# C64_PSU.net
KiCad netlist of a schematic drawn in EAGLE
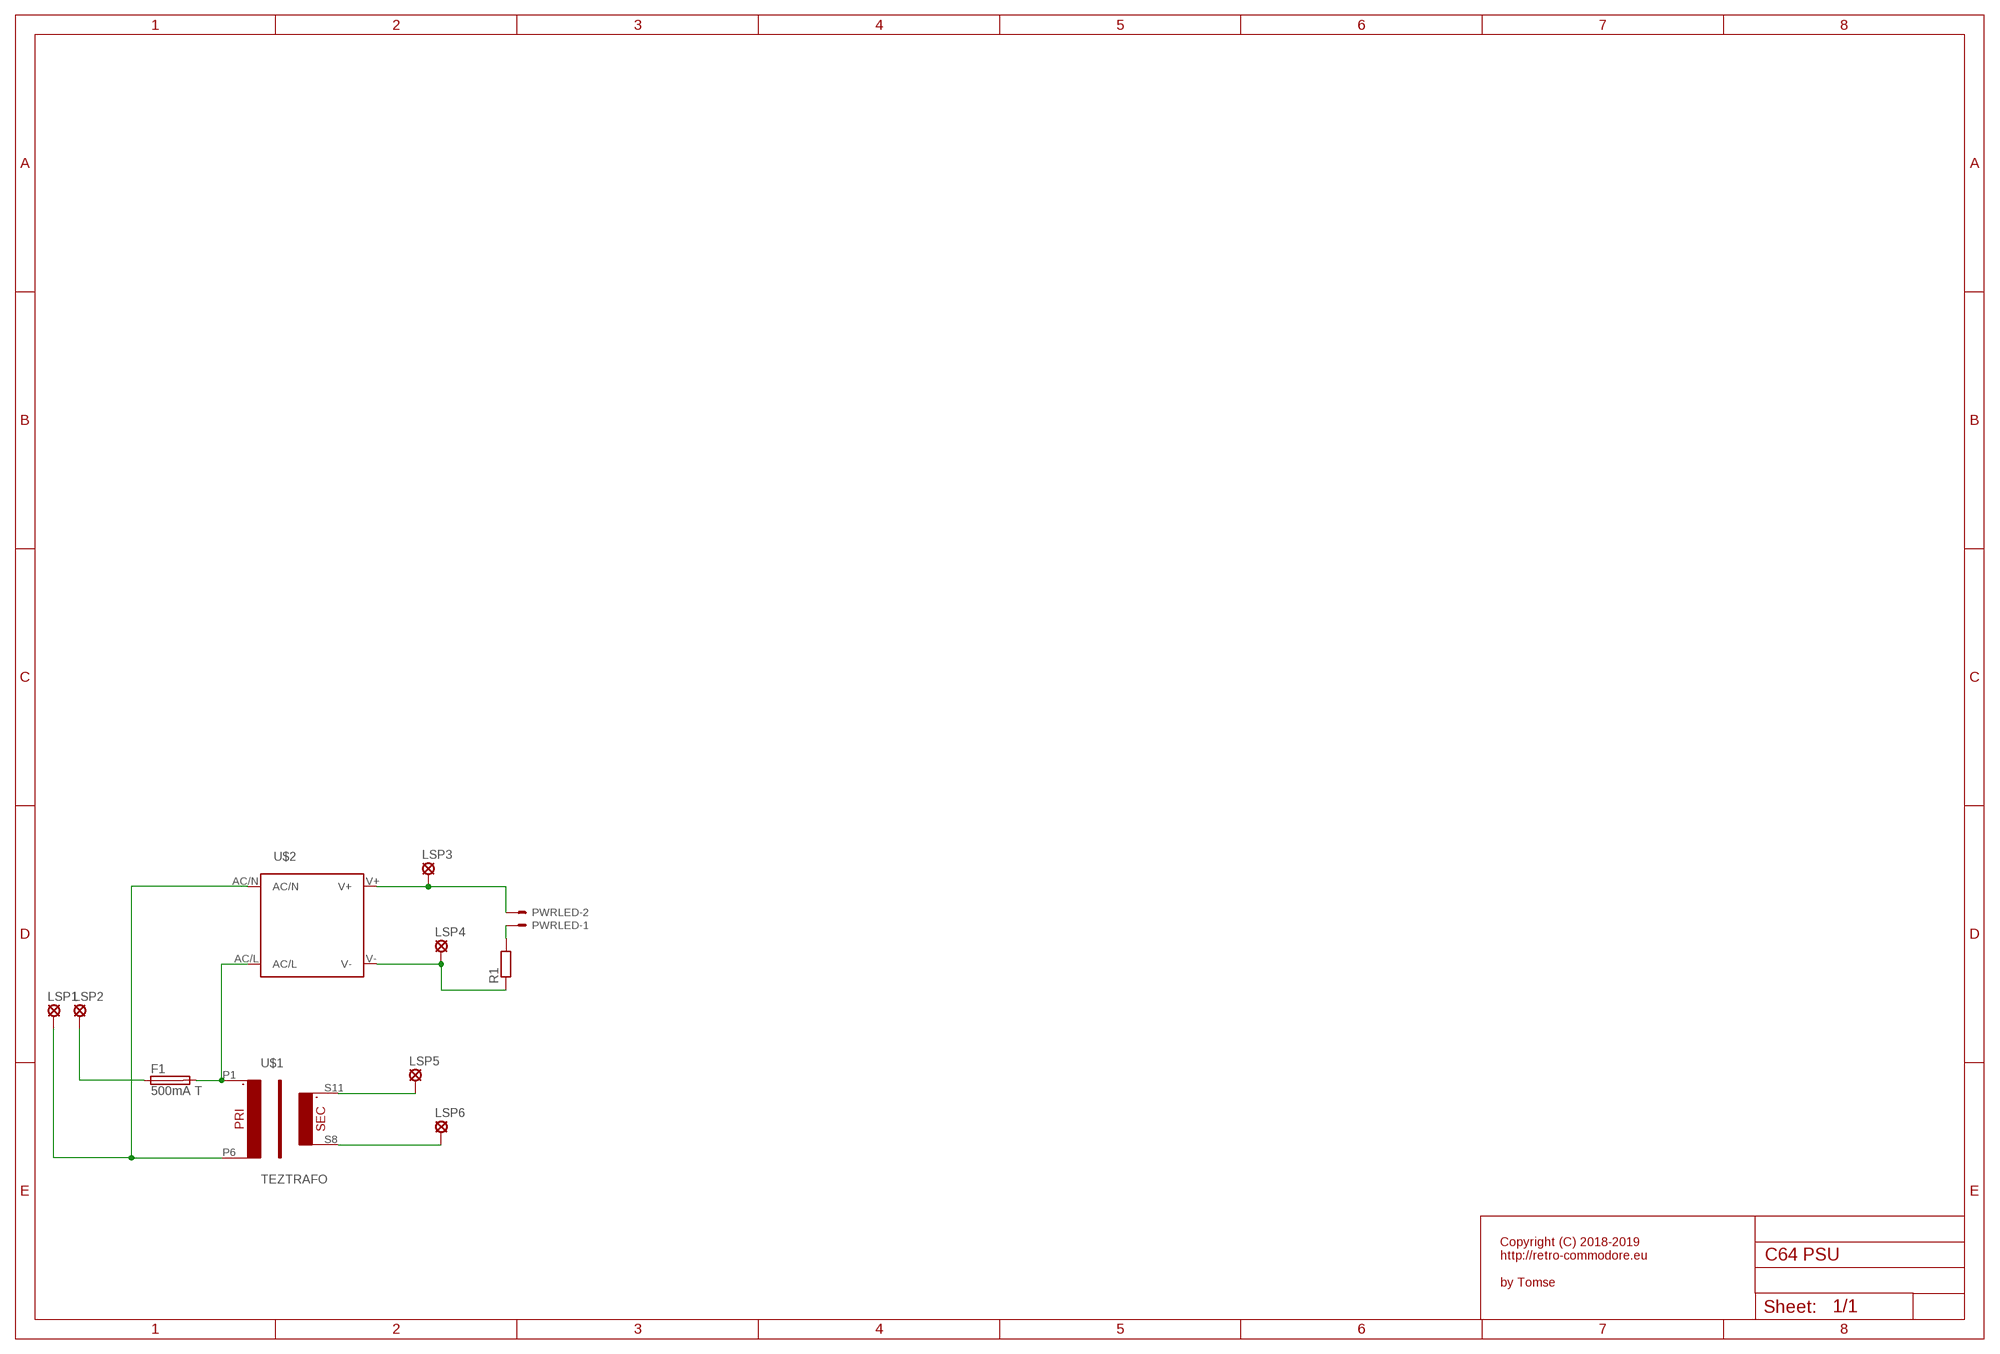
[diagram p0: schematic, sheet 1]

(export (version "E")
  (design (tool "Eeschema 10.0.6"))
  (components
    (comp (ref "F1")
      (value "500mA T")
      (footprint "eagle-import:SH22,5")
      (libsource (lib "eagle-import") (part "FUSESH22,5"))
    )
    (comp (ref "LSP1")
      (value "SE14")
      (footprint "eagle-import:SE14")
      (libsource (lib "eagle-import") (part "SE14"))
    )
    (comp (ref "LSP2")
      (value "SE14")
      (footprint "eagle-import:SE14")
      (libsource (lib "eagle-import") (part "SE14"))
    )
    (comp (ref "LSP3")
      (value "SE14")
      (footprint "eagle-import:SE14")
      (libsource (lib "eagle-import") (part "SE14"))
    )
    (comp (ref "LSP4")
      (value "SE14")
      (footprint "eagle-import:SE14")
      (libsource (lib "eagle-import") (part "SE14"))
    )
    (comp (ref "LSP5")
      (value "SE14")
      (footprint "eagle-import:SE14")
      (libsource (lib "eagle-import") (part "SE14"))
    )
    (comp (ref "LSP6")
      (value "SE14")
      (footprint "eagle-import:SE14")
      (libsource (lib "eagle-import") (part "SE14"))
    )
    (comp (ref "PWRLED")
      (value "22-23-2021")
      (footprint "eagle-import:22-23-2021")
      (fields (field (name "MF") "MOLEX"))
      (libsource (lib "eagle-import") (part "22-23-2021"))
    )
    (comp (ref "R1")
      (value "R-EU_0207/10")
      (footprint "eagle-import:0207_10")
      (libsource (lib "eagle-import") (part "R-EU_0207/10"))
    )
    (comp (ref "U$1")
      (value "TEZTRAFO")
      (footprint "eagle-import:TEZ10_D230_9V")
      (libsource (lib "eagle-import") (part "TEZTRAFO"))
    )
    (comp (ref "U$2")
      (value "IRM_15/20IRM_15/20")
      (footprint "eagle-import:IRM_15_20")
      (libsource (lib "eagle-import") (part "IRM_15/20IRM_15/20"))
    )
  )
  (nets
    (net (code "1") (name "Net-(F1-Pad1)") (class "Default")
      (node (ref "F1") (pin "1") (pinfunction "1_1") (pintype "passive"))
      (node (ref "LSP2") (pin "MP") (pinfunction "MP_MP") (pintype "passive"))
    )
    (net (code "2") (name "Net-(F1-Pad2)") (class "Default")
      (node (ref "F1") (pin "2") (pinfunction "2_2") (pintype "passive"))
      (node (ref "U$1") (pin "P1") (pinfunction "P1_P1") (pintype "power_in"))
      (node (ref "U$2") (pin "AC/L") (pinfunction "AC/L_AC/L") (pintype "input"))
    )
    (net (code "3") (name "Net-(LSP1-PadMP)") (class "Default")
      (node (ref "LSP1") (pin "MP") (pinfunction "MP_MP") (pintype "passive"))
      (node (ref "U$1") (pin "P6") (pinfunction "P6_P6") (pintype "power_in"))
      (node (ref "U$2") (pin "AC/N") (pinfunction "AC/N_AC/N") (pintype "input"))
    )
    (net (code "4") (name "Net-(LSP4-PadMP)") (class "Default")
      (node (ref "LSP4") (pin "MP") (pinfunction "MP_MP") (pintype "passive"))
      (node (ref "R1") (pin "1") (pinfunction "1_1") (pintype "passive"))
      (node (ref "U$2") (pin "V-") (pinfunction "V-_V-") (pintype "output"))
    )
    (net (code "5") (name "Net-(LSP5-PadMP)") (class "Default")
      (node (ref "LSP5") (pin "MP") (pinfunction "MP_MP") (pintype "passive"))
      (node (ref "U$1") (pin "S11") (pinfunction "S11_S11") (pintype "power_in"))
    )
    (net (code "6") (name "Net-(LSP6-PadMP)") (class "Default")
      (node (ref "LSP6") (pin "MP") (pinfunction "MP_MP") (pintype "passive"))
      (node (ref "U$1") (pin "S8") (pinfunction "S8_S8") (pintype "power_in"))
    )
    (net (code "7") (name "Net-(PWRLEDA-S)") (class "Default")
      (node (ref "PWRLED") (pin "1") (pinfunction "S_1") (pintype "passive"))
      (node (ref "R1") (pin "2") (pinfunction "2_2") (pintype "passive"))
    )
    (net (code "8") (name "Net-(PWRLEDB-S)") (class "Default")
      (node (ref "LSP3") (pin "MP") (pinfunction "MP_MP") (pintype "passive"))
      (node (ref "PWRLED") (pin "2") (pinfunction "S_2") (pintype "passive"))
      (node (ref "U$2") (pin "V+") (pinfunction "V+_V+") (pintype "output"))
    )
  )
)
